# FootSensor.net
KiCad netlist of a schematic drawn in EAGLE
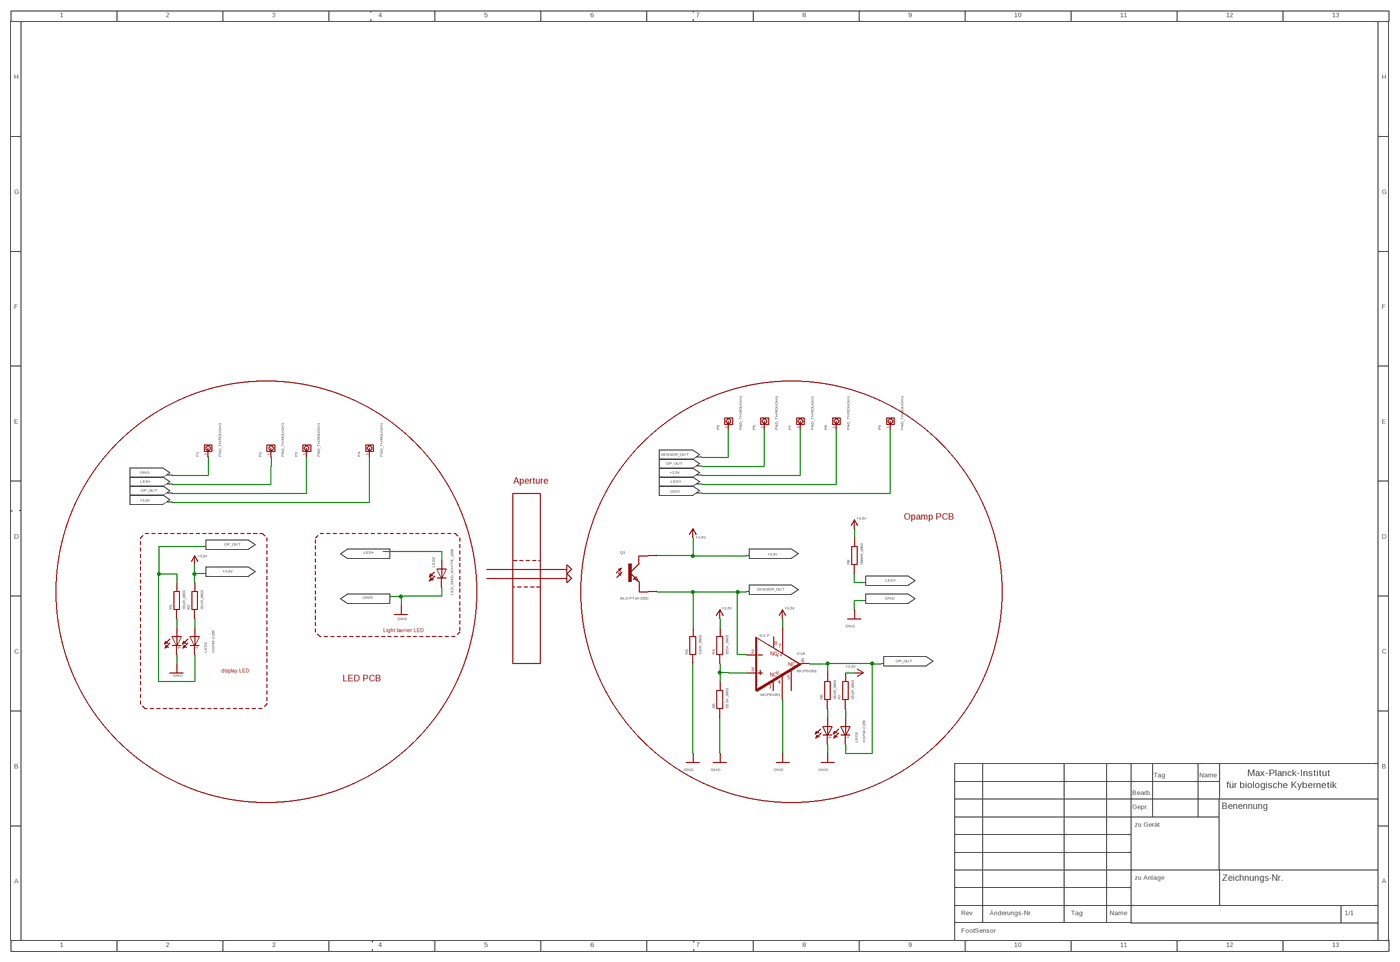
[diagram p0: schematic, sheet 1, overview]
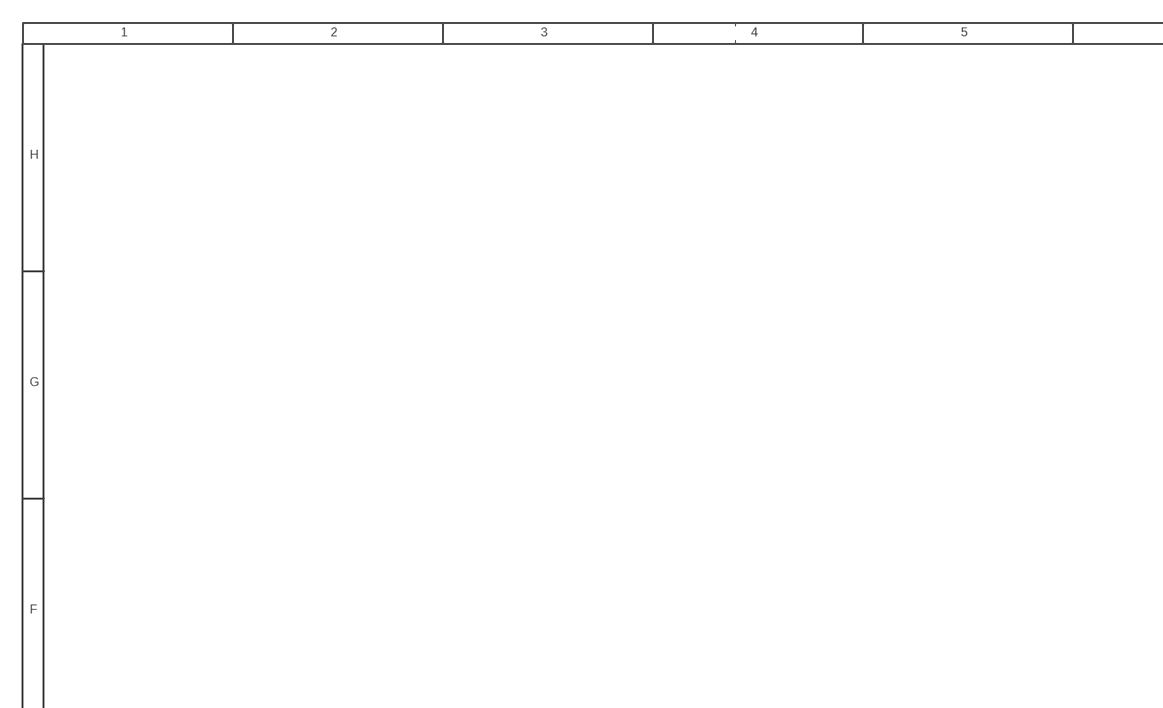
[diagram p1: schematic, sheet 1, part 1 of 4]
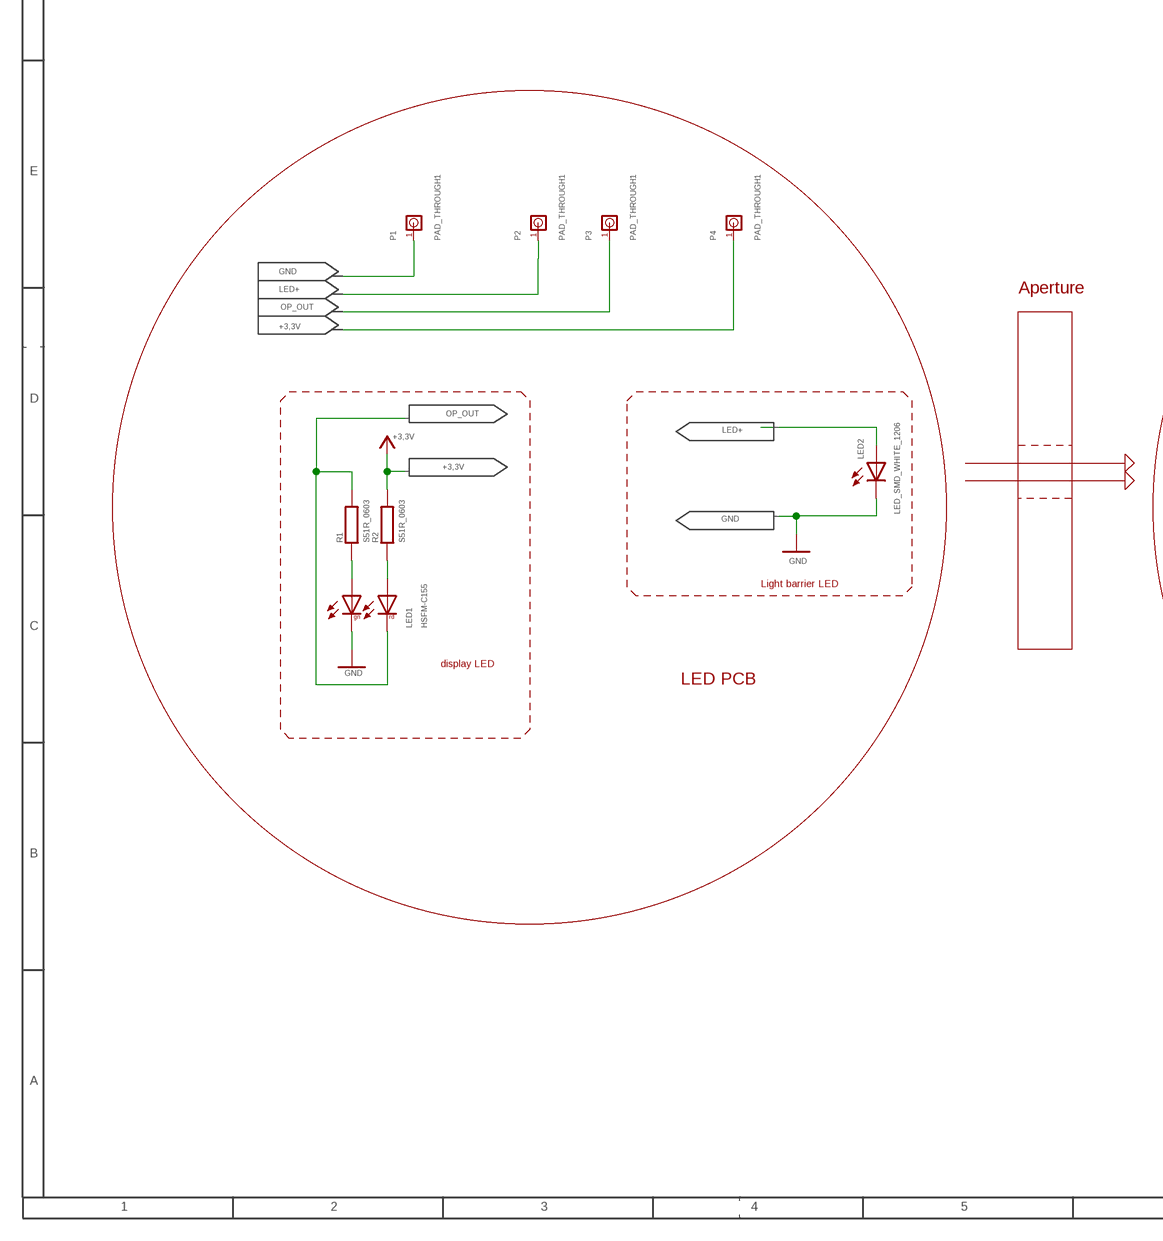
[diagram p2: schematic, sheet 1, part 2 of 4]
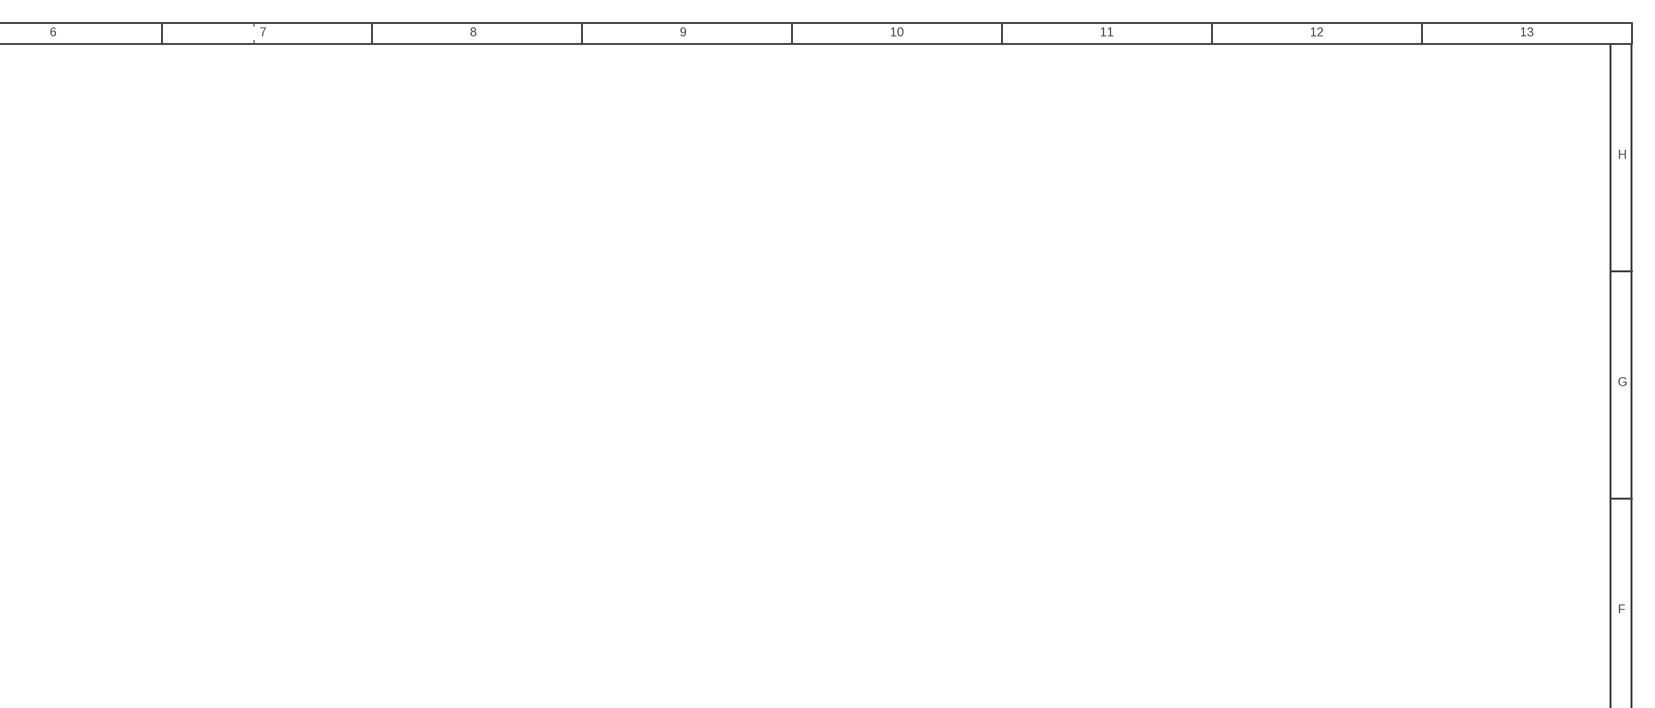
[diagram p3: schematic, sheet 1, part 3 of 4]
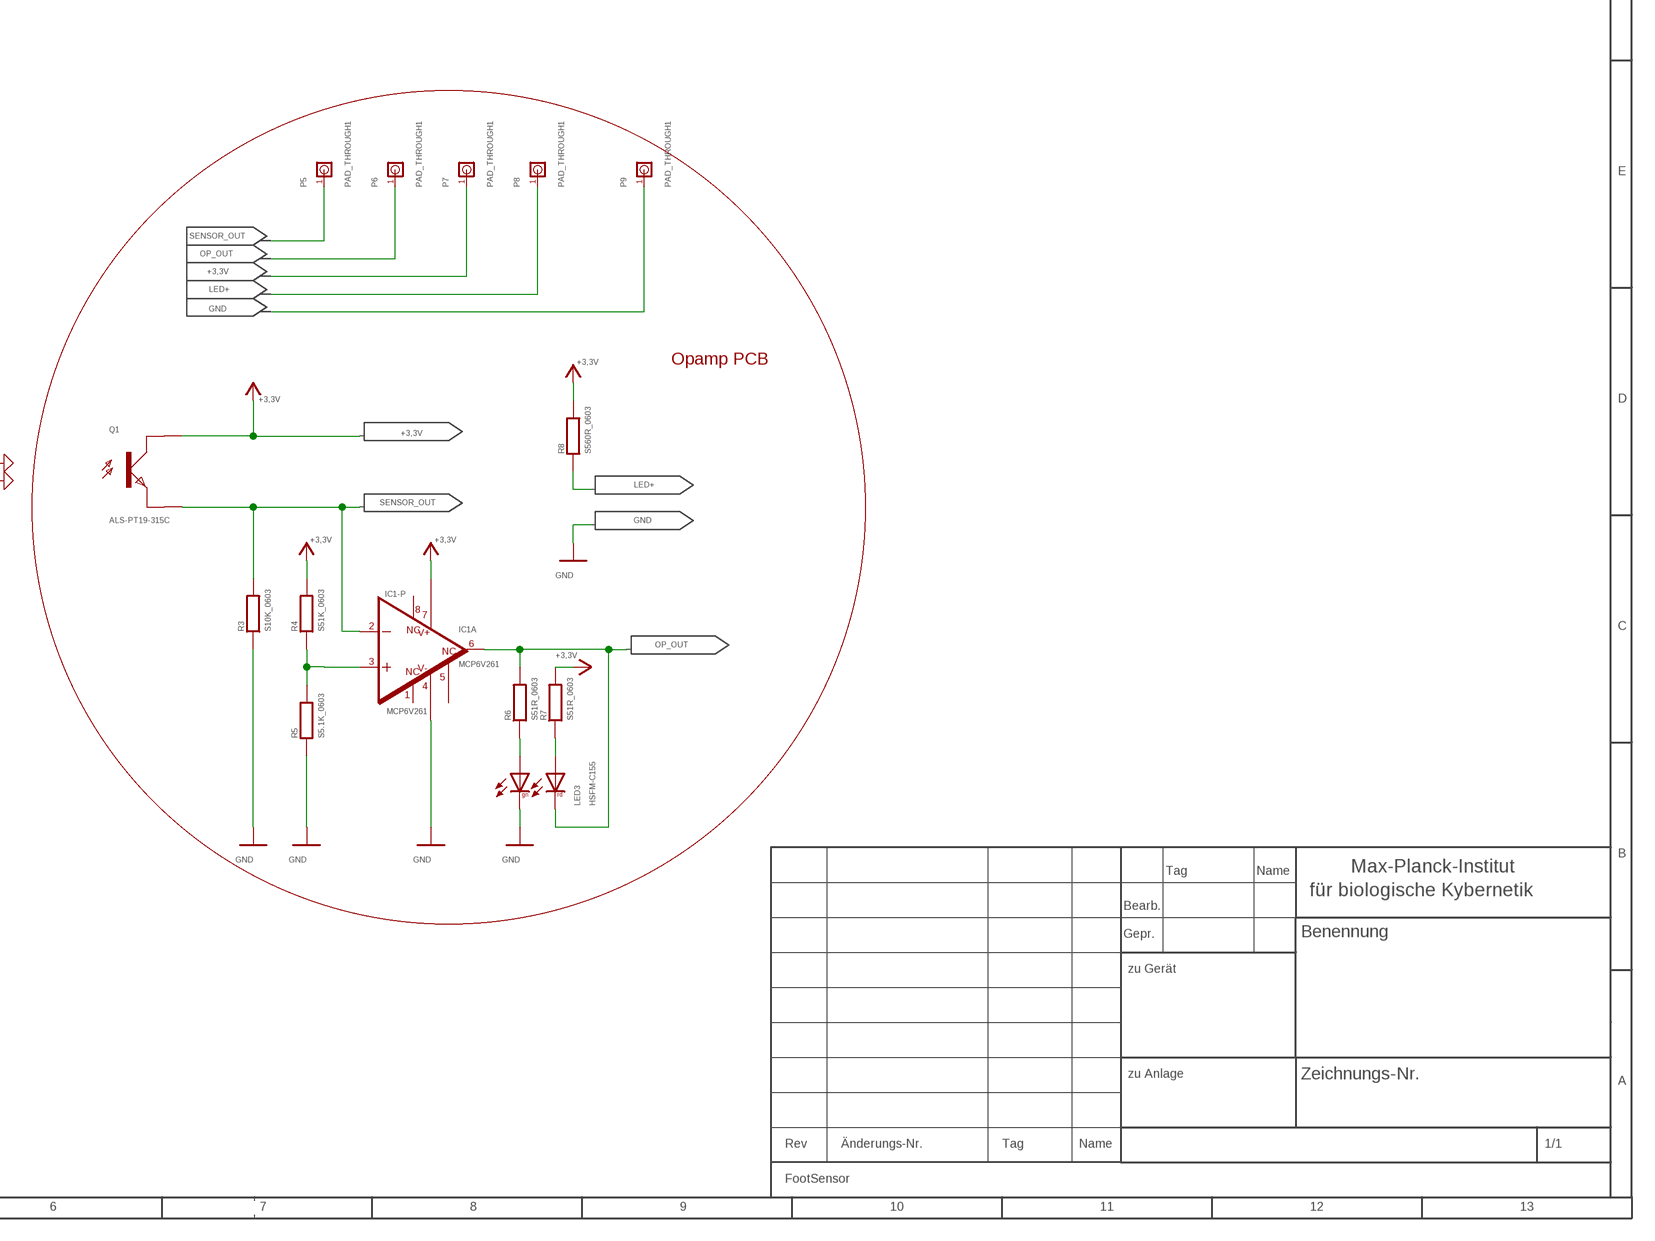
[diagram p4: schematic, sheet 1, part 4 of 4]

(export (version "E")
  (design (tool "Eeschema 10.0.6"))
  (components
    (comp (ref "IC1")
      (value "MCP6V261")
      (footprint "eagle-import:MSOP8")
      (libsource (lib "eagle-import") (part "MCP6V261"))
    )
    (comp (ref "LED1")
      (value "HSFM-C155")
      (footprint "eagle-import:3225")
      (libsource (lib "eagle-import") (part "HSFM-C155"))
    )
    (comp (ref "LED2")
      (value "LED_SMD_WHITE_1206")
      (footprint "eagle-import:1206C")
      (libsource (lib "eagle-import") (part "LED_SMD_WHITE_1206"))
    )
    (comp (ref "LED3")
      (value "HSFM-C155")
      (footprint "eagle-import:3225")
      (libsource (lib "eagle-import") (part "HSFM-C155"))
    )
    (comp (ref "P1")
      (value "PAD_THROUGH1")
      (footprint "eagle-import:PAD_TH_056X055")
      (libsource (lib "eagle-import") (part "PAD_THROUGH1"))
    )
    (comp (ref "P2")
      (value "PAD_THROUGH1")
      (footprint "eagle-import:PAD_TH_056X055")
      (libsource (lib "eagle-import") (part "PAD_THROUGH1"))
    )
    (comp (ref "P3")
      (value "PAD_THROUGH1")
      (footprint "eagle-import:PAD_TH_056X055")
      (libsource (lib "eagle-import") (part "PAD_THROUGH1"))
    )
    (comp (ref "P4")
      (value "PAD_THROUGH1")
      (footprint "eagle-import:PAD_TH_056X055")
      (libsource (lib "eagle-import") (part "PAD_THROUGH1"))
    )
    (comp (ref "P5")
      (value "PAD_THROUGH1")
      (footprint "eagle-import:PAD_TH_056X055")
      (libsource (lib "eagle-import") (part "PAD_THROUGH1"))
    )
    (comp (ref "P6")
      (value "PAD_THROUGH1")
      (footprint "eagle-import:PAD_TH_056X055")
      (libsource (lib "eagle-import") (part "PAD_THROUGH1"))
    )
    (comp (ref "P7")
      (value "PAD_THROUGH1")
      (footprint "eagle-import:PAD_TH_056X055")
      (libsource (lib "eagle-import") (part "PAD_THROUGH1"))
    )
    (comp (ref "P8")
      (value "PAD_THROUGH1")
      (footprint "eagle-import:PAD_TH_056X055")
      (libsource (lib "eagle-import") (part "PAD_THROUGH1"))
    )
    (comp (ref "P9")
      (value "PAD_THROUGH1")
      (footprint "eagle-import:PAD_TH_056X055")
      (libsource (lib "eagle-import") (part "PAD_THROUGH1"))
    )
    (comp (ref "Q1")
      (value "ALS-PT19-315C")
      (footprint "eagle-import:FOTOTRANSISTOR")
      (libsource (lib "eagle-import") (part "ALS-PT19-315C"))
    )
    (comp (ref "R1")
      (value "S51R_0603")
      (footprint "eagle-import:0603R")
      (libsource (lib "eagle-import") (part "S51R_0603"))
    )
    (comp (ref "R2")
      (value "S51R_0603")
      (footprint "eagle-import:0603R")
      (libsource (lib "eagle-import") (part "S51R_0603"))
    )
    (comp (ref "R3")
      (value "S10K_0603")
      (footprint "eagle-import:0603R")
      (libsource (lib "eagle-import") (part "S10K_0603"))
    )
    (comp (ref "R4")
      (value "S51K_0603")
      (footprint "eagle-import:0603R")
      (libsource (lib "eagle-import") (part "S51K_0603"))
    )
    (comp (ref "R5")
      (value "S5.1K_0603")
      (footprint "eagle-import:0603R")
      (libsource (lib "eagle-import") (part "S5.1K_0603"))
    )
    (comp (ref "R6")
      (value "S51R_0603")
      (footprint "eagle-import:0603R")
      (libsource (lib "eagle-import") (part "S51R_0603"))
    )
    (comp (ref "R7")
      (value "S51R_0603")
      (footprint "eagle-import:0603R")
      (libsource (lib "eagle-import") (part "S51R_0603"))
    )
    (comp (ref "R8")
      (value "S560R_0603")
      (footprint "eagle-import:0603R")
      (libsource (lib "eagle-import") (part "S560R_0603"))
    )
  )
  (nets
    (net (code "1") (name "+3,3V") (class "Default")
      (node (ref "IC1") (pin "7") (pinfunction "7_7") (pintype "bidirectional"))
      (node (ref "P4") (pin "P$1") (pinfunction "1_P$1") (pintype "passive"))
      (node (ref "P7") (pin "P$1") (pinfunction "1_P$1") (pintype "passive"))
      (node (ref "Q1") (pin "1") (pinfunction "C_1") (pintype "bidirectional"))
      (node (ref "R2") (pin "P$2") (pinfunction "2_P$2") (pintype "passive"))
      (node (ref "R4") (pin "P$2") (pinfunction "2_P$2") (pintype "passive"))
      (node (ref "R7") (pin "P$2") (pinfunction "2_P$2") (pintype "passive"))
      (node (ref "R8") (pin "P$2") (pinfunction "2_P$2") (pintype "passive"))
    )
    (net (code "2") (name "/LED+") (class "Default")
      (node (ref "LED2") (pin "+") (pinfunction "A1_+") (pintype "passive"))
      (node (ref "P2") (pin "P$1") (pinfunction "1_P$1") (pintype "passive"))
      (node (ref "P8") (pin "P$1") (pinfunction "1_P$1") (pintype "passive"))
      (node (ref "R8") (pin "P$1") (pinfunction "1_P$1") (pintype "passive"))
    )
    (net (code "3") (name "/OP_OUT") (class "Default")
      (node (ref "IC1") (pin "6") (pinfunction "6_6") (pintype "output"))
      (node (ref "LED1") (pin "4") (pinfunction "4_4") (pintype "passive"))
      (node (ref "LED3") (pin "4") (pinfunction "4_4") (pintype "passive"))
      (node (ref "P3") (pin "P$1") (pinfunction "1_P$1") (pintype "passive"))
      (node (ref "P6") (pin "P$1") (pinfunction "1_P$1") (pintype "passive"))
      (node (ref "R1") (pin "P$2") (pinfunction "2_P$2") (pintype "passive"))
      (node (ref "R6") (pin "P$2") (pinfunction "2_P$2") (pintype "passive"))
    )
    (net (code "4") (name "/SENSOR_OUT") (class "Default")
      (node (ref "IC1") (pin "2") (pinfunction "2_2") (pintype "input"))
      (node (ref "P5") (pin "P$1") (pinfunction "1_P$1") (pintype "passive"))
      (node (ref "Q1") (pin "2") (pinfunction "E_2") (pintype "bidirectional"))
      (node (ref "R3") (pin "P$2") (pinfunction "2_P$2") (pintype "passive"))
    )
    (net (code "5") (name "GND") (class "Default")
      (node (ref "IC1") (pin "4") (pinfunction "4_4") (pintype "bidirectional"))
      (node (ref "LED1") (pin "2") (pinfunction "2_2") (pintype "passive"))
      (node (ref "LED2") (pin "-") (pinfunction "C1_-") (pintype "passive"))
      (node (ref "LED3") (pin "2") (pinfunction "2_2") (pintype "passive"))
      (node (ref "P1") (pin "P$1") (pinfunction "1_P$1") (pintype "passive"))
      (node (ref "P9") (pin "P$1") (pinfunction "1_P$1") (pintype "passive"))
      (node (ref "R3") (pin "P$1") (pinfunction "1_P$1") (pintype "passive"))
      (node (ref "R5") (pin "P$1") (pinfunction "1_P$1") (pintype "passive"))
    )
    (net (code "6") (name "Net-(R1-1)") (class "Default")
      (node (ref "LED1") (pin "1") (pinfunction "1_1") (pintype "passive"))
      (node (ref "R1") (pin "P$1") (pinfunction "1_P$1") (pintype "passive"))
    )
    (net (code "7") (name "Net-(R2-1)") (class "Default")
      (node (ref "LED1") (pin "3") (pinfunction "3_3") (pintype "passive"))
      (node (ref "R2") (pin "P$1") (pinfunction "1_P$1") (pintype "passive"))
    )
    (net (code "8") (name "Net-(R4-1)") (class "Default")
      (node (ref "IC1") (pin "3") (pinfunction "3_3") (pintype "input"))
      (node (ref "R4") (pin "P$1") (pinfunction "1_P$1") (pintype "passive"))
      (node (ref "R5") (pin "P$2") (pinfunction "2_P$2") (pintype "passive"))
    )
    (net (code "9") (name "Net-(R6-1)") (class "Default")
      (node (ref "LED3") (pin "1") (pinfunction "1_1") (pintype "passive"))
      (node (ref "R6") (pin "P$1") (pinfunction "1_P$1") (pintype "passive"))
    )
    (net (code "10") (name "Net-(R7-1)") (class "Default")
      (node (ref "LED3") (pin "3") (pinfunction "3_3") (pintype "passive"))
      (node (ref "R7") (pin "P$1") (pinfunction "1_P$1") (pintype "passive"))
    )
    (net (code "11") (name "unconnected-(IC1-Pad1)") (class "Default")
      (node (ref "IC1") (pin "1") (pinfunction "1_1") (pintype "bidirectional"))
    )
    (net (code "12") (name "unconnected-(IC1-Pad5)") (class "Default")
      (node (ref "IC1") (pin "5") (pinfunction "5_5") (pintype "bidirectional"))
    )
    (net (code "13") (name "unconnected-(IC1-Pad8)") (class "Default")
      (node (ref "IC1") (pin "8") (pinfunction "8_8") (pintype "bidirectional"))
    )
  )
)
